# uPy_AudioCodec_00.net
KiCad netlist of a schematic drawn in EAGLE
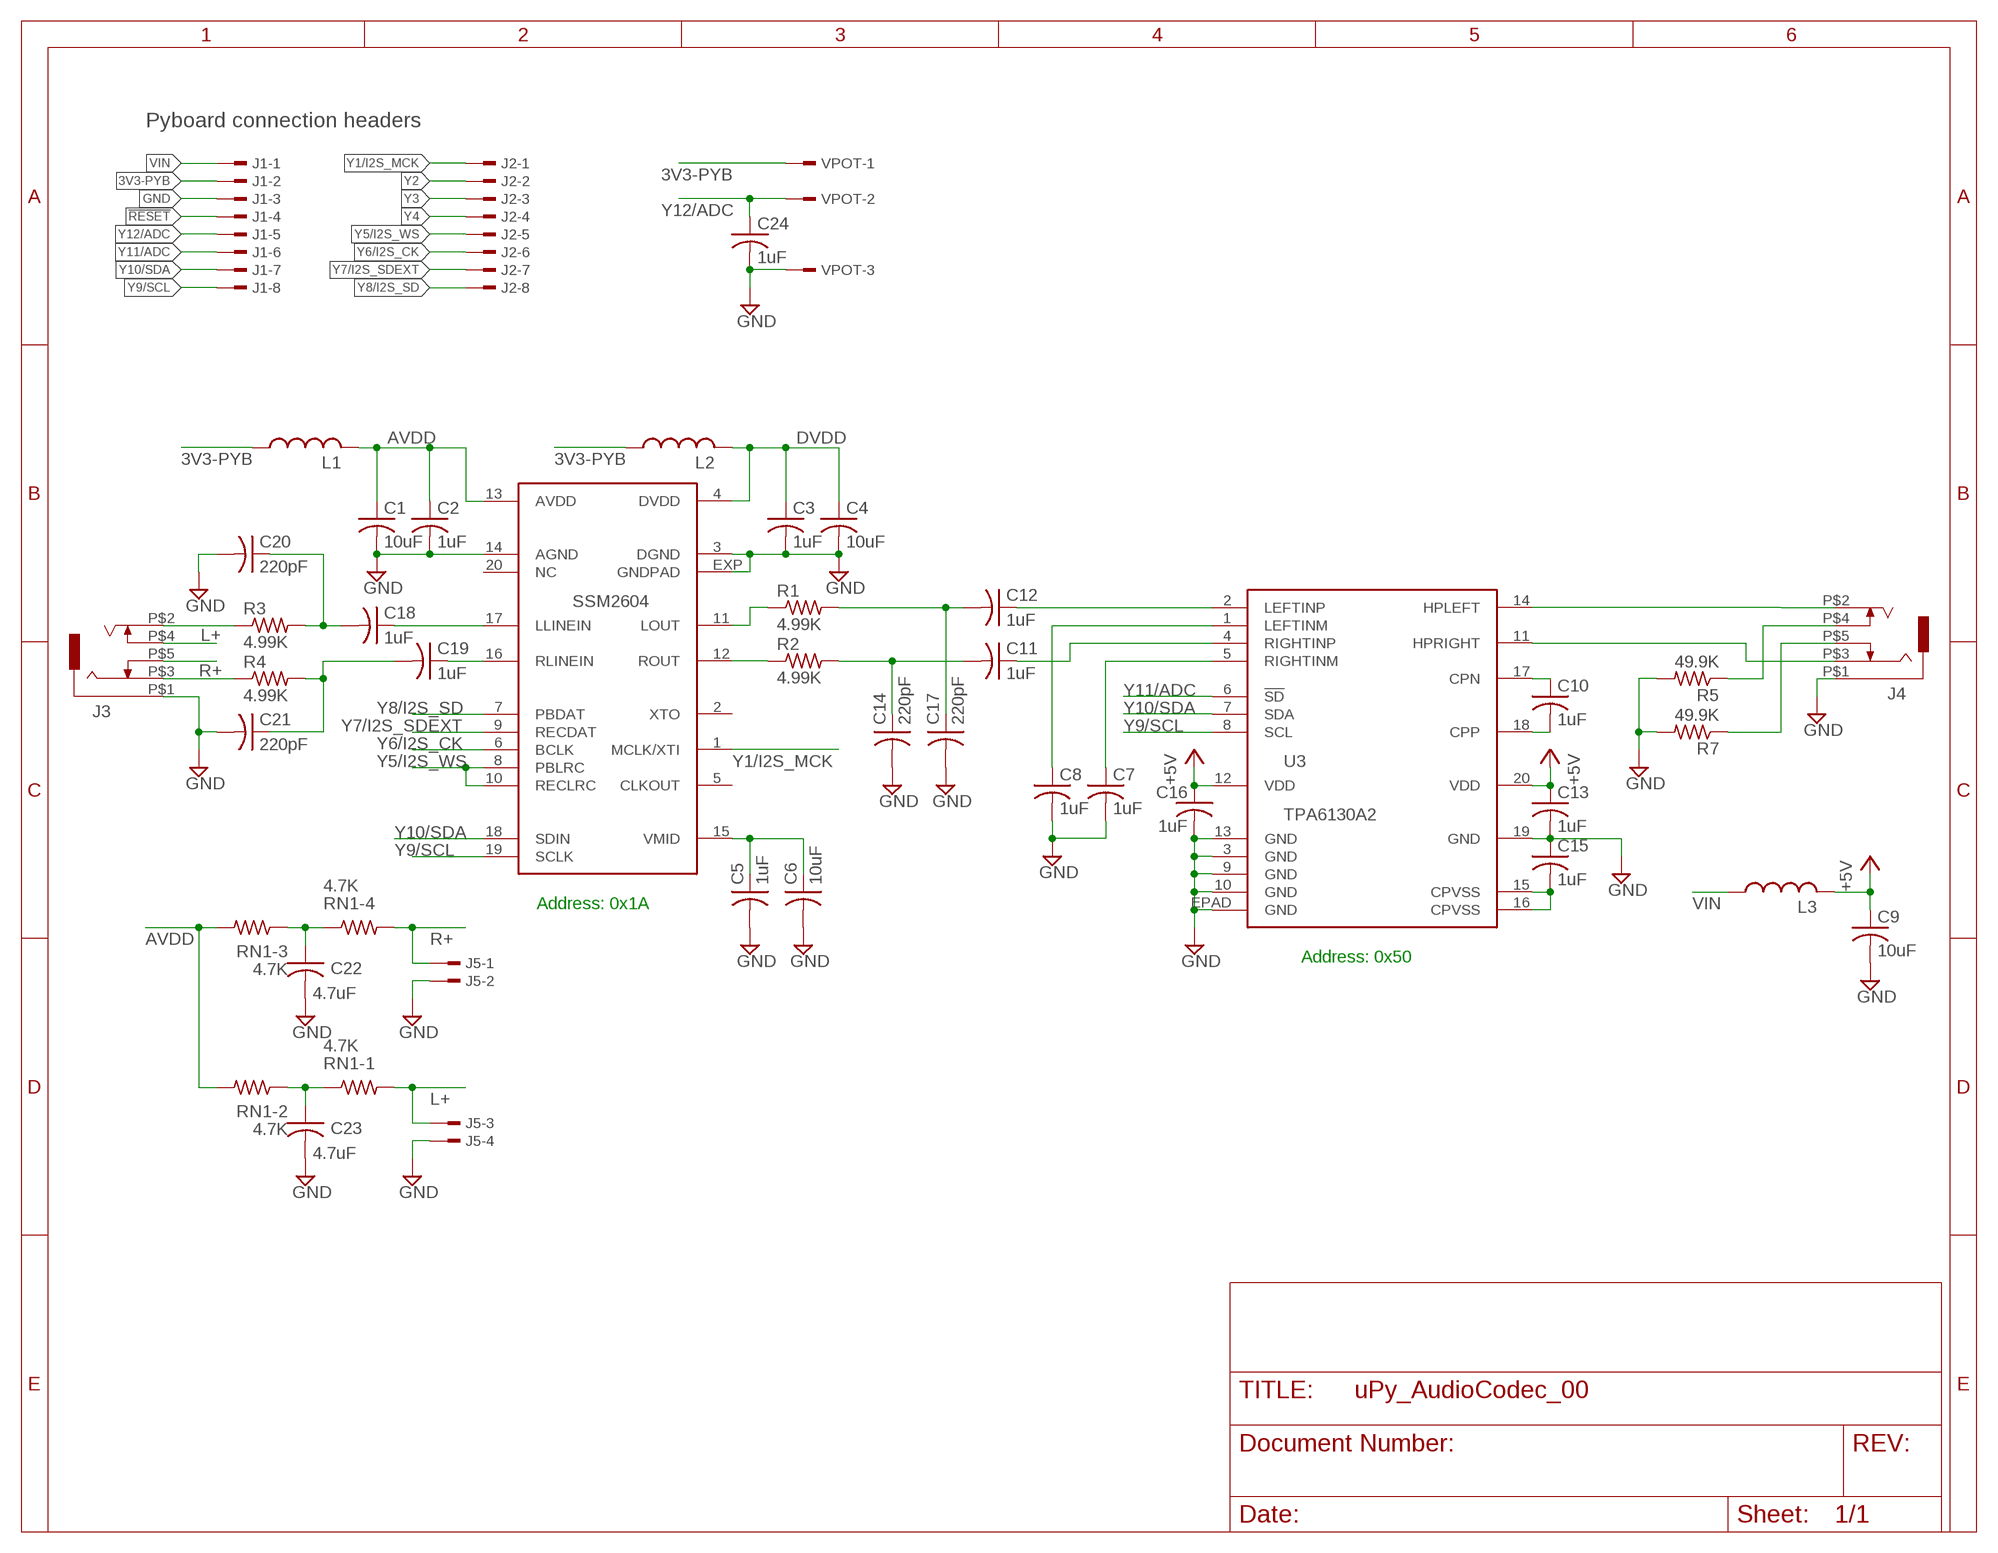
[diagram p0: schematic, sheet 1]

(export (version "E")
  (design (tool "Eeschema 10.0.6"))
  (components
    (comp (ref "C1")
      (value "10uF")
      (footprint "eagle-import:C0603K")
      (libsource (lib "eagle-import") (part "C-USC0603K"))
    )
    (comp (ref "C2")
      (value "1uF")
      (footprint "eagle-import:C0805K")
      (libsource (lib "eagle-import") (part "C-USC0805K"))
    )
    (comp (ref "C3")
      (value "1uF")
      (footprint "eagle-import:C0603K")
      (libsource (lib "eagle-import") (part "C-USC0603K"))
    )
    (comp (ref "C4")
      (value "10uF")
      (footprint "eagle-import:C0805K")
      (libsource (lib "eagle-import") (part "C-USC0805K"))
    )
    (comp (ref "C5")
      (value "1uF")
      (footprint "eagle-import:C0603K")
      (libsource (lib "eagle-import") (part "C-USC0603K"))
    )
    (comp (ref "C6")
      (value "10uF")
      (footprint "eagle-import:C0805K")
      (libsource (lib "eagle-import") (part "C-USC0805K"))
    )
    (comp (ref "C7")
      (value "1uF")
      (footprint "eagle-import:C0603K")
      (libsource (lib "eagle-import") (part "C-USC0603K"))
    )
    (comp (ref "C8")
      (value "1uF")
      (footprint "eagle-import:C0603K")
      (libsource (lib "eagle-import") (part "C-USC0603K"))
    )
    (comp (ref "C9")
      (value "10uF")
      (footprint "eagle-import:C0805K")
      (libsource (lib "eagle-import") (part "C-USC0805K"))
    )
    (comp (ref "C10")
      (value "1uF")
      (footprint "eagle-import:C0603K")
      (libsource (lib "eagle-import") (part "C-USC0603K"))
    )
    (comp (ref "C11")
      (value "1uF")
      (footprint "eagle-import:C0603K")
      (libsource (lib "eagle-import") (part "C-USC0603K"))
    )
    (comp (ref "C12")
      (value "1uF")
      (footprint "eagle-import:C0603K")
      (libsource (lib "eagle-import") (part "C-USC0603K"))
    )
    (comp (ref "C13")
      (value "1uF")
      (footprint "eagle-import:C0603K")
      (libsource (lib "eagle-import") (part "C-USC0603K"))
    )
    (comp (ref "C14")
      (value "220pF")
      (footprint "eagle-import:C0603K")
      (libsource (lib "eagle-import") (part "C-USC0603K"))
    )
    (comp (ref "C15")
      (value "1uF")
      (footprint "eagle-import:C0603K")
      (libsource (lib "eagle-import") (part "C-USC0603K"))
    )
    (comp (ref "C16")
      (value "1uF")
      (footprint "eagle-import:C0603K")
      (libsource (lib "eagle-import") (part "C-USC0603K"))
    )
    (comp (ref "C17")
      (value "220pF")
      (footprint "eagle-import:C0603K")
      (libsource (lib "eagle-import") (part "C-USC0603K"))
    )
    (comp (ref "C18")
      (value "1uF")
      (footprint "eagle-import:C0603K")
      (libsource (lib "eagle-import") (part "C-USC0603K"))
    )
    (comp (ref "C19")
      (value "1uF")
      (footprint "eagle-import:C0603K")
      (libsource (lib "eagle-import") (part "C-USC0603K"))
    )
    (comp (ref "C20")
      (value "220pF")
      (footprint "eagle-import:C0603K")
      (libsource (lib "eagle-import") (part "C-USC0603K"))
    )
    (comp (ref "C21")
      (value "220pF")
      (footprint "eagle-import:C0603K")
      (libsource (lib "eagle-import") (part "C-USC0603K"))
    )
    (comp (ref "C22")
      (value "4.7uF")
      (footprint "eagle-import:C0603K")
      (libsource (lib "eagle-import") (part "C-USC0603K"))
    )
    (comp (ref "C23")
      (value "4.7uF")
      (footprint "eagle-import:C0603K")
      (libsource (lib "eagle-import") (part "C-USC0603K"))
    )
    (comp (ref "C24")
      (value "1uF")
      (footprint "eagle-import:C0603K")
      (libsource (lib "eagle-import") (part "C-USC0603K"))
    )
    (comp (ref "J1")
      (value "TSW-108-02-S-S-MOD")
      (footprint "eagle-import:TSW-108-02-S-S-MOD")
      (libsource (lib "eagle-import") (part "TSW-108-02-S-S-MOD"))
    )
    (comp (ref "J2")
      (value "TSW-108-02-S-S-MOD")
      (footprint "eagle-import:TSW-108-02-S-S-MOD")
      (libsource (lib "eagle-import") (part "TSW-108-02-S-S-MOD"))
    )
    (comp (ref "J3")
      (value "CON-JACK-STEREO")
      (footprint "eagle-import:CON-JACK-SJ1-3515-SMT")
      (libsource (lib "eagle-import") (part "CON-JACK-STEREO"))
    )
    (comp (ref "J4")
      (value "CON-JACK-STEREO")
      (footprint "eagle-import:CON-JACK-SJ1-3515-SMT")
      (libsource (lib "eagle-import") (part "CON-JACK-STEREO"))
    )
    (comp (ref "J5")
      (value "TSW-104-02-S-S")
      (footprint "eagle-import:TSW-104-02-S-S-MOD")
      (libsource (lib "eagle-import") (part "TSW-104-02-S-S"))
    )
    (comp (ref "L1")
      (value "L-USL3216C")
      (footprint "eagle-import:L3216C")
      (libsource (lib "eagle-import") (part "L-USL3216C"))
    )
    (comp (ref "L2")
      (value "L-USL3216C")
      (footprint "eagle-import:L3216C")
      (libsource (lib "eagle-import") (part "L-USL3216C"))
    )
    (comp (ref "L3")
      (value "L-USL3216C")
      (footprint "eagle-import:L3216C")
      (libsource (lib "eagle-import") (part "L-USL3216C"))
    )
    (comp (ref "R1")
      (value "4.99K")
      (footprint "eagle-import:R0805")
      (libsource (lib "eagle-import") (part "R-US_R0805"))
    )
    (comp (ref "R2")
      (value "4.99K")
      (footprint "eagle-import:R0805")
      (libsource (lib "eagle-import") (part "R-US_R0805"))
    )
    (comp (ref "R3")
      (value "4.99K")
      (footprint "eagle-import:R0805")
      (libsource (lib "eagle-import") (part "R-US_R0805"))
    )
    (comp (ref "R4")
      (value "4.99K")
      (footprint "eagle-import:R0805")
      (libsource (lib "eagle-import") (part "R-US_R0805"))
    )
    (comp (ref "R5")
      (value "49.9K")
      (footprint "eagle-import:R0805")
      (libsource (lib "eagle-import") (part "R-US_R0805"))
    )
    (comp (ref "R7")
      (value "49.9K")
      (footprint "eagle-import:R0805")
      (libsource (lib "eagle-import") (part "R-US_R0805"))
    )
    (comp (ref "RN1")
      (value "4.7K")
      (footprint "eagle-import:CTS-742C083+")
      (libsource (lib "eagle-import") (part "4R-ISONET-BB"))
    )
    (comp (ref "U1")
      (value "SSM2604-1")
      (footprint "eagle-import:LFCSP20-1")
      (libsource (lib "eagle-import") (part "SSM2604-1"))
    )
    (comp (ref "U3")
      (value "TPA6130A2")
      (footprint "eagle-import:QFN20-EP")
      (libsource (lib "eagle-import") (part "TPA6130A2"))
    )
    (comp (ref "VPOT")
      (value "TSW-103-02-S-S")
      (footprint "eagle-import:TSW-103-02-S-S-MOD")
      (libsource (lib "eagle-import") (part "TSW-103-02-S-S"))
    )
  )
  (nets
    (net (code "1") (name "+5V") (class "Default")
      (node (ref "C13") (pin "1") (pinfunction "1_1") (pintype "passive"))
      (node (ref "C16") (pin "1") (pinfunction "1_1") (pintype "passive"))
      (node (ref "C9") (pin "1") (pinfunction "1_1") (pintype "passive"))
      (node (ref "L3") (pin "2") (pinfunction "2_2") (pintype "passive"))
      (node (ref "U3") (pin "12") (pinfunction "VDD_12") (pintype "power_in"))
      (node (ref "U3") (pin "20") (pinfunction "VDD_20") (pintype "power_in"))
    )
    (net (code "2") (name "/AVDD") (class "Default")
      (node (ref "C1") (pin "1") (pinfunction "1_1") (pintype "passive"))
      (node (ref "C2") (pin "1") (pinfunction "1_1") (pintype "passive"))
      (node (ref "L1") (pin "2") (pinfunction "2_2") (pintype "passive"))
      (node (ref "RN1") (pin "P$6") (pinfunction "2_P$6") (pintype "passive"))
      (node (ref "RN1") (pin "P$7") (pinfunction "2_P$7") (pintype "passive"))
      (node (ref "U1") (pin "13") (pinfunction "AVDD_13") (pintype "power_in"))
    )
    (net (code "3") (name "/DVDD") (class "Default")
      (node (ref "C3") (pin "1") (pinfunction "1_1") (pintype "passive"))
      (node (ref "C4") (pin "1") (pinfunction "1_1") (pintype "passive"))
      (node (ref "L2") (pin "2") (pinfunction "2_2") (pintype "passive"))
      (node (ref "U1") (pin "4") (pinfunction "DVDD_4") (pintype "power_in"))
    )
    (net (code "4") (name "/L+") (class "Default")
      (node (ref "J3") (pin "P$4") (pinfunction "TIP_SW_P$4") (pintype "passive"))
      (node (ref "J5") (pin "3") (pinfunction "1_3") (pintype "passive"))
      (node (ref "RN1") (pin "P$8") (pinfunction "2_P$8") (pintype "passive"))
    )
    (net (code "5") (name "/R+") (class "Default")
      (node (ref "J3") (pin "P$5") (pinfunction "RING_SW_P$5") (pintype "passive"))
      (node (ref "J5") (pin "1") (pinfunction "1_1") (pintype "passive"))
      (node (ref "RN1") (pin "P$5") (pinfunction "2_P$5") (pintype "passive"))
    )
    (net (code "6") (name "/~{RESET}") (class "Default")
      (node (ref "J1") (pin "4") (pinfunction "1_4") (pintype "passive"))
    )
    (net (code "7") (name "3V3-PYB") (class "Default")
      (node (ref "J1") (pin "2") (pinfunction "1_2") (pintype "passive"))
      (node (ref "L1") (pin "1") (pinfunction "1_1") (pintype "passive"))
      (node (ref "L2") (pin "1") (pinfunction "1_1") (pintype "passive"))
      (node (ref "VPOT") (pin "1") (pinfunction "1_1") (pintype "passive"))
    )
    (net (code "8") (name "GND") (class "Default")
      (node (ref "C1") (pin "2") (pinfunction "2_2") (pintype "passive"))
      (node (ref "C13") (pin "2") (pinfunction "2_2") (pintype "passive"))
      (node (ref "C14") (pin "2") (pinfunction "2_2") (pintype "passive"))
      (node (ref "C15") (pin "1") (pinfunction "1_1") (pintype "passive"))
      (node (ref "C16") (pin "2") (pinfunction "2_2") (pintype "passive"))
      (node (ref "C17") (pin "2") (pinfunction "2_2") (pintype "passive"))
      (node (ref "C2") (pin "2") (pinfunction "2_2") (pintype "passive"))
      (node (ref "C20") (pin "2") (pinfunction "2_2") (pintype "passive"))
      (node (ref "C21") (pin "2") (pinfunction "2_2") (pintype "passive"))
      (node (ref "C22") (pin "2") (pinfunction "2_2") (pintype "passive"))
      (node (ref "C23") (pin "2") (pinfunction "2_2") (pintype "passive"))
      (node (ref "C24") (pin "2") (pinfunction "2_2") (pintype "passive"))
      (node (ref "C3") (pin "2") (pinfunction "2_2") (pintype "passive"))
      (node (ref "C4") (pin "2") (pinfunction "2_2") (pintype "passive"))
      (node (ref "C5") (pin "2") (pinfunction "2_2") (pintype "passive"))
      (node (ref "C6") (pin "2") (pinfunction "2_2") (pintype "passive"))
      (node (ref "C7") (pin "2") (pinfunction "2_2") (pintype "passive"))
      (node (ref "C8") (pin "2") (pinfunction "2_2") (pintype "passive"))
      (node (ref "C9") (pin "2") (pinfunction "2_2") (pintype "passive"))
      (node (ref "J1") (pin "3") (pinfunction "1_3") (pintype "passive"))
      (node (ref "J3") (pin "P$1") (pinfunction "SLEEVE_P$1") (pintype "passive"))
      (node (ref "J4") (pin "P$1") (pinfunction "SLEEVE_P$1") (pintype "passive"))
      (node (ref "J5") (pin "2") (pinfunction "1_2") (pintype "passive"))
      (node (ref "J5") (pin "4") (pinfunction "1_4") (pintype "passive"))
      (node (ref "R5") (pin "2") (pinfunction "2_2") (pintype "passive"))
      (node (ref "R7") (pin "2") (pinfunction "2_2") (pintype "passive"))
      (node (ref "U1") (pin "14") (pinfunction "AGND_14") (pintype "power_in"))
      (node (ref "U1") (pin "3") (pinfunction "DGND_3") (pintype "power_in"))
      (node (ref "U1") (pin "EXP") (pinfunction "GNDPAD_EXP") (pintype "power_in"))
      (node (ref "U3") (pin "10") (pinfunction "GND_10") (pintype "power_in"))
      (node (ref "U3") (pin "13") (pinfunction "GND_13") (pintype "power_in"))
      (node (ref "U3") (pin "19") (pinfunction "GND_19") (pintype "power_in"))
      (node (ref "U3") (pin "3") (pinfunction "GND_3") (pintype "power_in"))
      (node (ref "U3") (pin "9") (pinfunction "GND_9") (pintype "power_in"))
      (node (ref "U3") (pin "EPAD") (pinfunction "GND_EPAD") (pintype "power_in"))
      (node (ref "VPOT") (pin "3") (pinfunction "1_3") (pintype "passive"))
    )
    (net (code "9") (name "Net-(C11-Pad2)") (class "Default")
      (node (ref "C11") (pin "2") (pinfunction "2_2") (pintype "passive"))
      (node (ref "C14") (pin "1") (pinfunction "1_1") (pintype "passive"))
      (node (ref "R2") (pin "2") (pinfunction "2_2") (pintype "passive"))
    )
    (net (code "10") (name "Net-(C12-Pad2)") (class "Default")
      (node (ref "C12") (pin "2") (pinfunction "2_2") (pintype "passive"))
      (node (ref "C17") (pin "1") (pinfunction "1_1") (pintype "passive"))
      (node (ref "R1") (pin "2") (pinfunction "2_2") (pintype "passive"))
    )
    (net (code "11") (name "Net-(C15-Pad2)") (class "Default")
      (node (ref "C15") (pin "2") (pinfunction "2_2") (pintype "passive"))
      (node (ref "U3") (pin "15") (pinfunction "CPVSS_15") (pintype "power_in"))
      (node (ref "U3") (pin "16") (pinfunction "CPVSS_16") (pintype "power_in"))
    )
    (net (code "12") (name "Net-(C18-Pad2)") (class "Default")
      (node (ref "C18") (pin "2") (pinfunction "2_2") (pintype "passive"))
      (node (ref "C20") (pin "1") (pinfunction "1_1") (pintype "passive"))
      (node (ref "R3") (pin "2") (pinfunction "2_2") (pintype "passive"))
    )
    (net (code "13") (name "Net-(C19-Pad2)") (class "Default")
      (node (ref "C19") (pin "2") (pinfunction "2_2") (pintype "passive"))
      (node (ref "C21") (pin "1") (pinfunction "1_1") (pintype "passive"))
      (node (ref "R4") (pin "2") (pinfunction "2_2") (pintype "passive"))
    )
    (net (code "14") (name "Net-(J3-RING)") (class "Default")
      (node (ref "J3") (pin "P$3") (pinfunction "RING_P$3") (pintype "passive"))
      (node (ref "R4") (pin "1") (pinfunction "1_1") (pintype "passive"))
    )
    (net (code "15") (name "Net-(J3-TIP)") (class "Default")
      (node (ref "J3") (pin "P$2") (pinfunction "TIP_P$2") (pintype "passive"))
      (node (ref "R3") (pin "1") (pinfunction "1_1") (pintype "passive"))
    )
    (net (code "16") (name "Net-(J4-RING)") (class "Default")
      (node (ref "J4") (pin "P$3") (pinfunction "RING_P$3") (pintype "passive"))
      (node (ref "U3") (pin "11") (pinfunction "HPRIGHT_11") (pintype "output"))
    )
    (net (code "17") (name "Net-(J4-RING_SW)") (class "Default")
      (node (ref "J4") (pin "P$5") (pinfunction "RING_SW_P$5") (pintype "passive"))
      (node (ref "R7") (pin "1") (pinfunction "1_1") (pintype "passive"))
    )
    (net (code "18") (name "Net-(J4-TIP)") (class "Default")
      (node (ref "J4") (pin "P$2") (pinfunction "TIP_P$2") (pintype "passive"))
      (node (ref "U3") (pin "14") (pinfunction "HPLEFT_14") (pintype "output"))
    )
    (net (code "19") (name "Net-(J4-TIP_SW)") (class "Default")
      (node (ref "J4") (pin "P$4") (pinfunction "TIP_SW_P$4") (pintype "passive"))
      (node (ref "R5") (pin "1") (pinfunction "1_1") (pintype "passive"))
    )
    (net (code "20") (name "Net-(RN1A-1)") (class "Default")
      (node (ref "C23") (pin "1") (pinfunction "1_1") (pintype "passive"))
      (node (ref "RN1") (pin "P$1") (pinfunction "1_P$1") (pintype "passive"))
      (node (ref "RN1") (pin "P$2") (pinfunction "1_P$2") (pintype "passive"))
    )
    (net (code "21") (name "Net-(RN1C-1)") (class "Default")
      (node (ref "C22") (pin "1") (pinfunction "1_1") (pintype "passive"))
      (node (ref "RN1") (pin "P$3") (pinfunction "1_P$3") (pintype "passive"))
      (node (ref "RN1") (pin "P$4") (pinfunction "1_P$4") (pintype "passive"))
    )
    (net (code "22") (name "Net-(U1-LLINEIN)") (class "Default")
      (node (ref "C18") (pin "1") (pinfunction "1_1") (pintype "passive"))
      (node (ref "U1") (pin "17") (pinfunction "LLINEIN_17") (pintype "input"))
    )
    (net (code "23") (name "Net-(U1-LOUT)") (class "Default")
      (node (ref "R1") (pin "1") (pinfunction "1_1") (pintype "passive"))
      (node (ref "U1") (pin "11") (pinfunction "LOUT_11") (pintype "output"))
    )
    (net (code "24") (name "Net-(U1-RLINEIN)") (class "Default")
      (node (ref "C19") (pin "1") (pinfunction "1_1") (pintype "passive"))
      (node (ref "U1") (pin "16") (pinfunction "RLINEIN_16") (pintype "input"))
    )
    (net (code "25") (name "Net-(U1-ROUT)") (class "Default")
      (node (ref "R2") (pin "1") (pinfunction "1_1") (pintype "passive"))
      (node (ref "U1") (pin "12") (pinfunction "ROUT_12") (pintype "output"))
    )
    (net (code "26") (name "Net-(U1-VMID)") (class "Default")
      (node (ref "C5") (pin "1") (pinfunction "1_1") (pintype "passive"))
      (node (ref "C6") (pin "1") (pinfunction "1_1") (pintype "passive"))
      (node (ref "U1") (pin "15") (pinfunction "VMID_15") (pintype "power_in"))
    )
    (net (code "27") (name "Net-(U3-CPN)") (class "Default")
      (node (ref "C10") (pin "1") (pinfunction "1_1") (pintype "passive"))
      (node (ref "U3") (pin "17") (pinfunction "CPN_17") (pintype "power_in"))
    )
    (net (code "28") (name "Net-(U3-CPP)") (class "Default")
      (node (ref "C10") (pin "2") (pinfunction "2_2") (pintype "passive"))
      (node (ref "U3") (pin "18") (pinfunction "CPP_18") (pintype "power_in"))
    )
    (net (code "29") (name "Net-(U3-LEFTINM)") (class "Default")
      (node (ref "C8") (pin "1") (pinfunction "1_1") (pintype "passive"))
      (node (ref "U3") (pin "1") (pinfunction "LEFTINM_1") (pintype "input"))
    )
    (net (code "30") (name "Net-(U3-LEFTINP)") (class "Default")
      (node (ref "C12") (pin "1") (pinfunction "1_1") (pintype "passive"))
      (node (ref "U3") (pin "2") (pinfunction "LEFTINP_2") (pintype "input"))
    )
    (net (code "31") (name "Net-(U3-RIGHTINM)") (class "Default")
      (node (ref "C7") (pin "1") (pinfunction "1_1") (pintype "passive"))
      (node (ref "U3") (pin "5") (pinfunction "RIGHTINM_5") (pintype "input"))
    )
    (net (code "32") (name "Net-(U3-RIGHTINP)") (class "Default")
      (node (ref "C11") (pin "1") (pinfunction "1_1") (pintype "passive"))
      (node (ref "U3") (pin "4") (pinfunction "RIGHTINP_4") (pintype "input"))
    )
    (net (code "33") (name "VIN") (class "Default")
      (node (ref "J1") (pin "1") (pinfunction "1_1") (pintype "passive"))
      (node (ref "L3") (pin "1") (pinfunction "1_1") (pintype "passive"))
    )
    (net (code "34") (name "Y1{slash}I2S_MCK") (class "Default")
      (node (ref "J2") (pin "1") (pinfunction "1_1") (pintype "passive"))
      (node (ref "U1") (pin "1") (pinfunction "MCLK/XTI_1") (pintype "input"))
    )
    (net (code "35") (name "Y2") (class "Default")
      (node (ref "J2") (pin "2") (pinfunction "1_2") (pintype "passive"))
    )
    (net (code "36") (name "Y3") (class "Default")
      (node (ref "J2") (pin "3") (pinfunction "1_3") (pintype "passive"))
    )
    (net (code "37") (name "Y4") (class "Default")
      (node (ref "J2") (pin "4") (pinfunction "1_4") (pintype "passive"))
    )
    (net (code "38") (name "Y5{slash}I2S_WS") (class "Default")
      (node (ref "J2") (pin "5") (pinfunction "1_5") (pintype "passive"))
      (node (ref "U1") (pin "10") (pinfunction "RECLRC_10") (pintype "output"))
      (node (ref "U1") (pin "8") (pinfunction "PBLRC_8") (pintype "input"))
    )
    (net (code "39") (name "Y6{slash}I2S_CK") (class "Default")
      (node (ref "J2") (pin "6") (pinfunction "1_6") (pintype "passive"))
      (node (ref "U1") (pin "6") (pinfunction "BCLK_6") (pintype "input"))
    )
    (net (code "40") (name "Y7{slash}I2S_SDEXT") (class "Default")
      (node (ref "J2") (pin "7") (pinfunction "1_7") (pintype "passive"))
      (node (ref "U1") (pin "9") (pinfunction "RECDAT_9") (pintype "power_in"))
    )
    (net (code "41") (name "Y8{slash}I2S_SD") (class "Default")
      (node (ref "J2") (pin "8") (pinfunction "1_8") (pintype "passive"))
      (node (ref "U1") (pin "7") (pinfunction "PBDAT_7") (pintype "power_in"))
    )
    (net (code "42") (name "Y9{slash}SCL") (class "Default")
      (node (ref "J1") (pin "8") (pinfunction "1_8") (pintype "passive"))
      (node (ref "U1") (pin "19") (pinfunction "SCLK_19") (pintype "output"))
      (node (ref "U3") (pin "8") (pinfunction "SCL_8") (pintype "input"))
    )
    (net (code "43") (name "Y10{slash}SDA") (class "Default")
      (node (ref "J1") (pin "7") (pinfunction "1_7") (pintype "passive"))
      (node (ref "U1") (pin "18") (pinfunction "SDIN_18") (pintype "input"))
      (node (ref "U3") (pin "7") (pinfunction "SDA_7") (pintype "bidirectional"))
    )
    (net (code "44") (name "Y11{slash}ADC") (class "Default")
      (node (ref "J1") (pin "6") (pinfunction "1_6") (pintype "passive"))
      (node (ref "U3") (pin "6") (pinfunction "~{SD}_6") (pintype "input"))
    )
    (net (code "45") (name "Y12{slash}ADC") (class "Default")
      (node (ref "C24") (pin "1") (pinfunction "1_1") (pintype "passive"))
      (node (ref "J1") (pin "5") (pinfunction "1_5") (pintype "passive"))
      (node (ref "VPOT") (pin "2") (pinfunction "1_2") (pintype "passive"))
    )
    (net (code "46") (name "unconnected-(U1-CLKOUT-Pad5)") (class "Default")
      (node (ref "U1") (pin "5") (pinfunction "CLKOUT_5") (pintype "output"))
    )
    (net (code "47") (name "unconnected-(U1-NC-Pad20)") (class "Default")
      (node (ref "U1") (pin "20") (pinfunction "NC_20") (pintype "input"))
    )
    (net (code "48") (name "unconnected-(U1-XTO-Pad2)") (class "Default")
      (node (ref "U1") (pin "2") (pinfunction "XTO_2") (pintype "output"))
    )
  )
)
